# MCU.net
KiCad netlist of a schematic drawn in Altium Designer
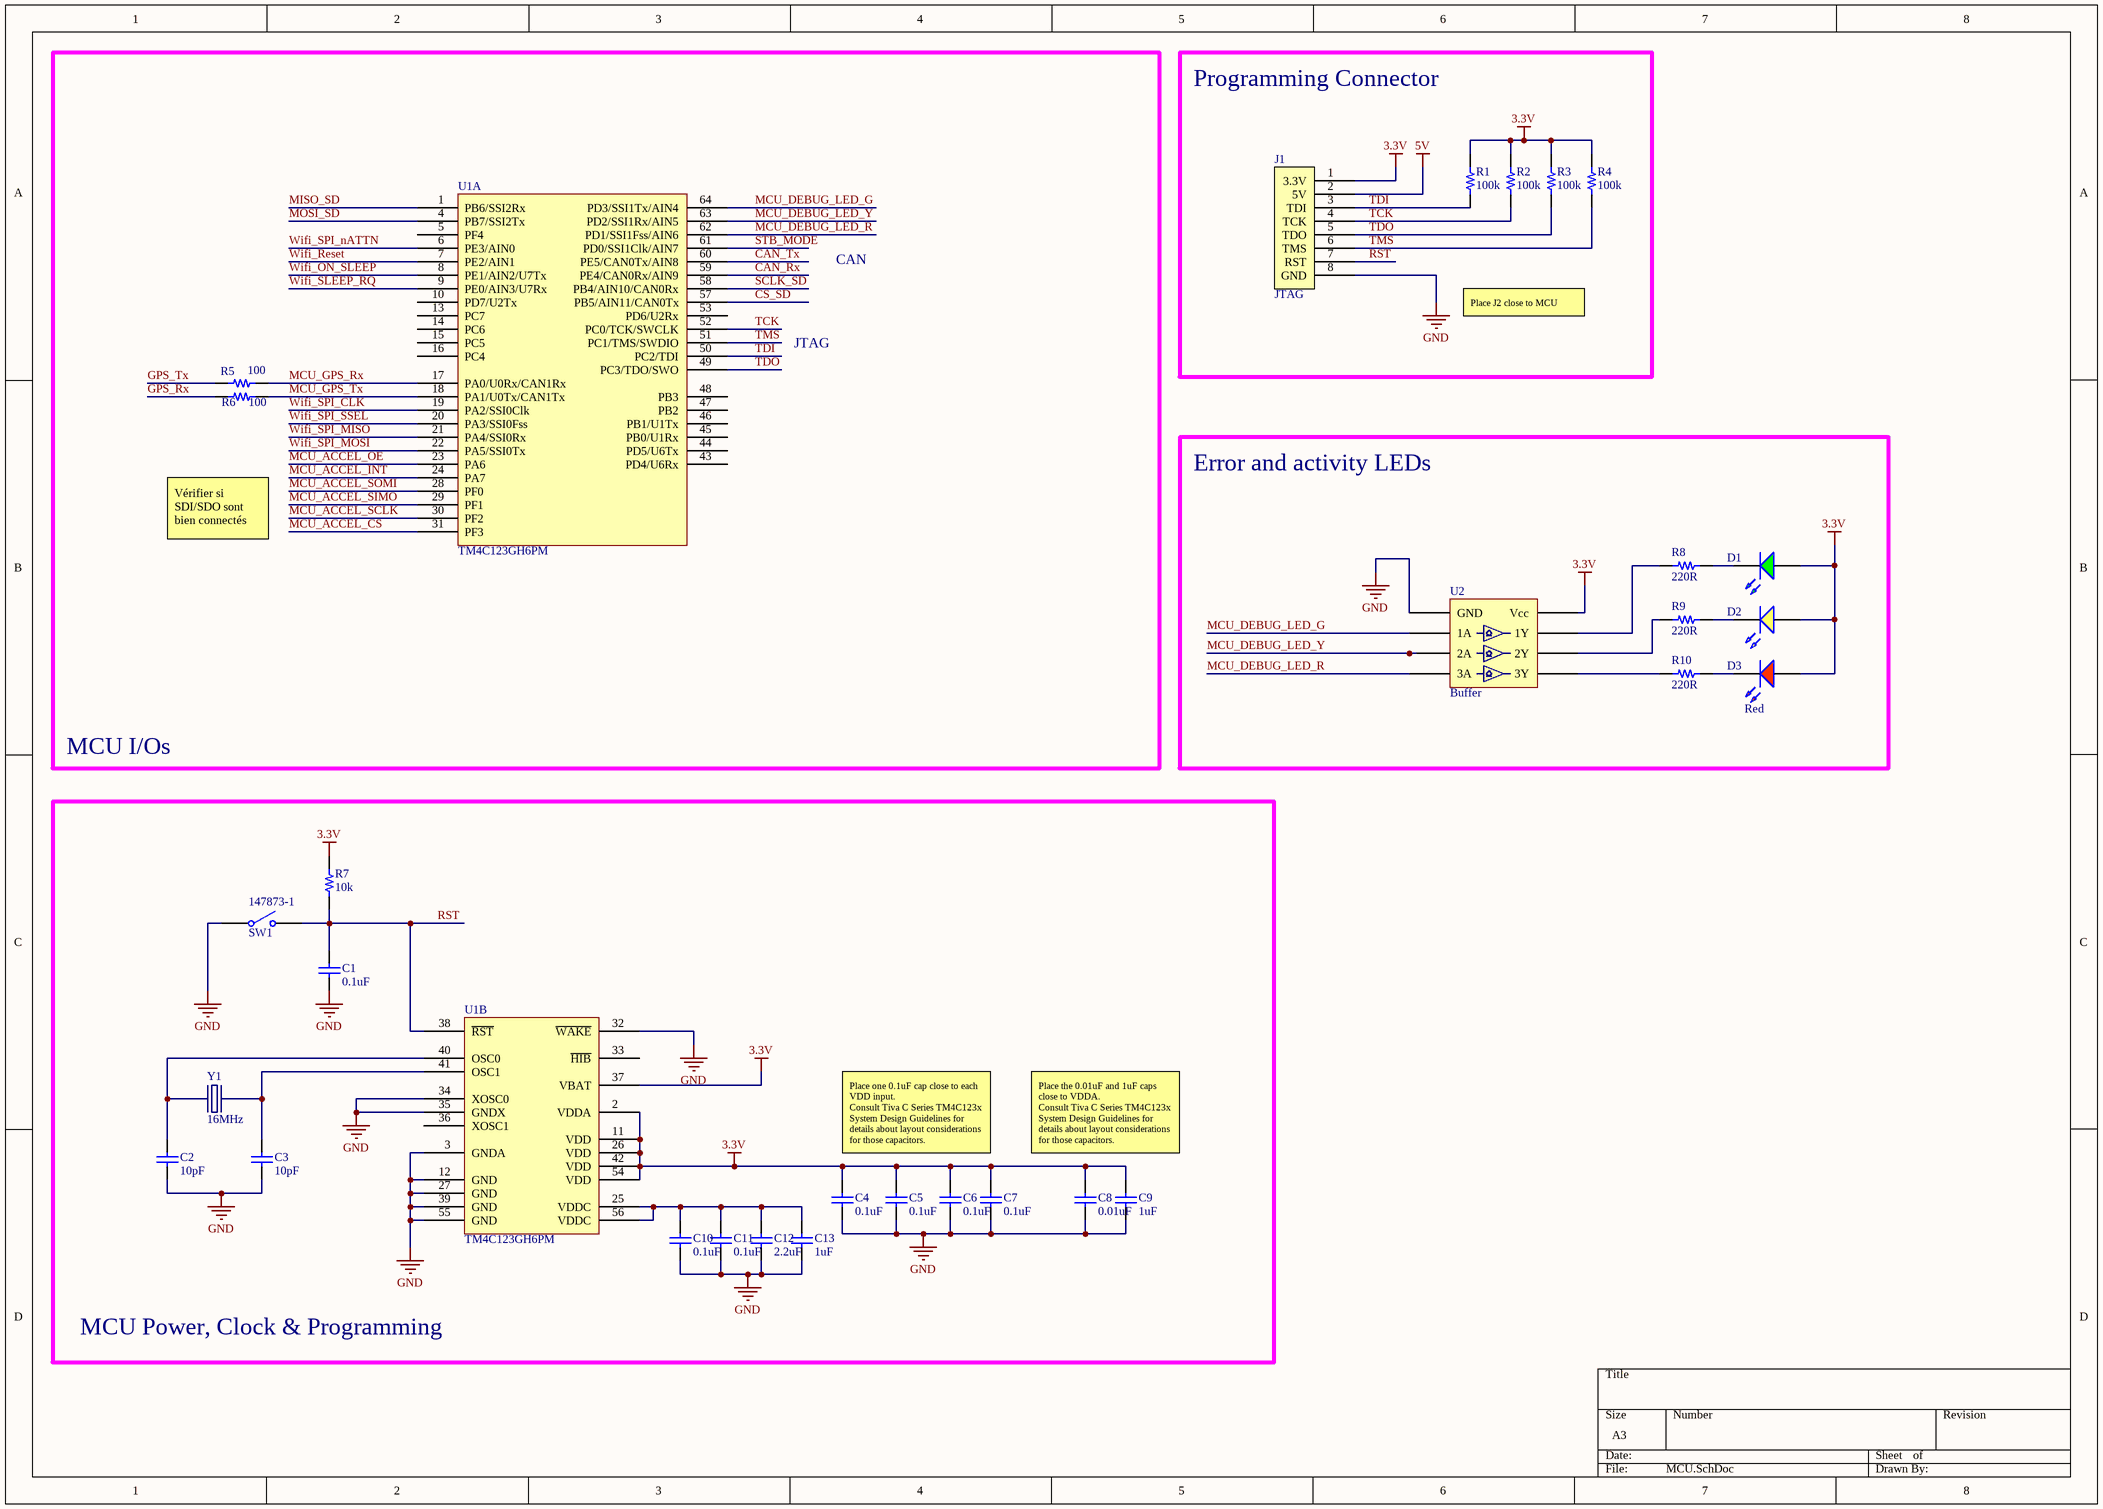
[diagram p0: MCU.SchDoc]

(export (version "E")
  (design (tool "Eeschema 10.0.6"))
  (components
    (comp (ref "C1")
      (value "0.1uF")
      (footprint "Capacitors:C0603")
      (description "0.1uF ceramic capacitor")
      (fields (field (name "MANUFACTURER") "TDK Corporation") (field (name "TOLERANCE") "10%"))
      (libsource (lib "Capacitors") (part "CAP CER 0603 0.1uF 50V C0G 10%"))
    )
    (comp (ref "C2")
      (value "10pF")
      (footprint "Capacitors:C0603")
      (description "10pF ceramic capacitor")
      (fields (field (name "MANUFACTURER") "TDK Corporation") (field (name "TOLERANCE") "5%"))
      (libsource (lib "Capacitors") (part "CAP CER 0603 10pF 50V C0G 5%"))
    )
    (comp (ref "C3")
      (value "10pF")
      (footprint "Capacitors:C0603")
      (description "10pF ceramic capacitor")
      (fields (field (name "MANUFACTURER") "TDK Corporation") (field (name "TOLERANCE") "5%"))
      (libsource (lib "Capacitors") (part "CAP CER 0603 10pF 50V C0G 5%"))
    )
    (comp (ref "C4")
      (value "0.1uF")
      (footprint "Capacitors:C0603")
      (description "0.1uF ceramic capacitor")
      (fields (field (name "MANUFACTURER") "TDK Corporation") (field (name "TOLERANCE") "10%"))
      (libsource (lib "Capacitors") (part "CAP CER 0603 0.1uF 50V C0G 10%"))
    )
    (comp (ref "C5")
      (value "0.1uF")
      (footprint "Capacitors:C0603")
      (description "0.1uF ceramic capacitor")
      (fields (field (name "MANUFACTURER") "TDK Corporation") (field (name "TOLERANCE") "10%"))
      (libsource (lib "Capacitors") (part "CAP CER 0603 0.1uF 50V C0G 10%"))
    )
    (comp (ref "C6")
      (value "0.1uF")
      (footprint "Capacitors:C0603")
      (description "0.1uF ceramic capacitor")
      (fields (field (name "MANUFACTURER") "TDK Corporation") (field (name "TOLERANCE") "10%"))
      (libsource (lib "Capacitors") (part "CAP CER 0603 0.1uF 50V C0G 10%"))
    )
    (comp (ref "C7")
      (value "0.1uF")
      (footprint "Capacitors:C0603")
      (description "0.1uF ceramic capacitor")
      (fields (field (name "MANUFACTURER") "TDK Corporation") (field (name "TOLERANCE") "10%"))
      (libsource (lib "Capacitors") (part "CAP CER 0603 0.1uF 50V C0G 10%"))
    )
    (comp (ref "C8")
      (value "0.01uF")
      (footprint "Capacitors:C0603")
      (description "0.01uF ceramic capacitor")
      (fields (field (name "MANUFACTURER") "TDK Corporation") (field (name "TOLERANCE") "10%"))
      (libsource (lib "Capacitors") (part "CAP CER 0603 0.01uF 50V X7R 10%"))
    )
    (comp (ref "C9")
      (value "1uF")
      (footprint "Capacitors:C0603")
      (description "1uF ceramic capacitor")
      (fields (field (name "MANUFACTURER") "TDK Corporation") (field (name "TOLERANCE") "20%"))
      (libsource (lib "Capacitors") (part "CAP CER 0603 1uF 25V X7R 20%"))
    )
    (comp (ref "C10")
      (value "0.1uF")
      (footprint "Capacitors:C0603")
      (description "0.1uF ceramic capacitor")
      (fields (field (name "MANUFACTURER") "TDK Corporation") (field (name "TOLERANCE") "10%"))
      (libsource (lib "Capacitors") (part "CAP CER 0603 0.1uF 50V C0G 10%"))
    )
    (comp (ref "C11")
      (value "0.1uF")
      (footprint "Capacitors:C0603")
      (description "0.1uF ceramic capacitor")
      (fields (field (name "MANUFACTURER") "TDK Corporation") (field (name "TOLERANCE") "10%"))
      (libsource (lib "Capacitors") (part "CAP CER 0603 0.1uF 50V C0G 10%"))
    )
    (comp (ref "C12")
      (value "2.2uF")
      (footprint "Capacitors:C0603")
      (description "2.2uF ceramic capacitor")
      (fields (field (name "MANUFACTURER") "TDK Corporation") (field (name "TOLERANCE") "10%"))
      (libsource (lib "Capacitors") (part "CAP CER 0603 2.2uF 6.3V X7R 10%"))
    )
    (comp (ref "C13")
      (value "1uF")
      (footprint "Capacitors:C0603")
      (description "1uF ceramic capacitor")
      (fields (field (name "MANUFACTURER") "TDK Corporation") (field (name "TOLERANCE") "20%"))
      (libsource (lib "Capacitors") (part "CAP CER 0603 1uF 25V X7R 20%"))
    )
    (comp (ref "D1")
      (value "Green LED")
      (footprint "LED1206")
      (description "Green LED 1206")
      (fields (field (name "MANUFACTURER") "Liteon") (field (name "PART_NUMBER") "LTST-C150KGKT"))
      (libsource (lib "Diodes") (part "LTST-C150KGKT"))
    )
    (comp (ref "D2")
      (value "Yellow")
      (footprint "LED1206")
      (description "Yellow LED 1206")
      (fields (field (name "MANUFACTURER") "Liteon") (field (name "PART_NUMBER") "LTST-C150KSKT"))
      (libsource (lib "Diodes") (part "LTST-C150KSKT"))
    )
    (comp (ref "D3")
      (value "Red")
      (footprint "LED1206")
      (description "Red LED 1206")
      (fields (field (name "MANUFACTURER") "Liteon") (field (name "PART_NUMBER") "LTST-C150KRKT"))
      (libsource (lib "Diodes") (part "LTST-C150KRKT"))
    )
    (comp (ref "J1")
      (value "JTAG")
      (footprint "Connectors:JTAG_Header")
      (description "JTAG header, MCU programming")
      (libsource (lib "Connectors") (part "JTAG_Header"))
    )
    (comp (ref "R1")
      (value "100k")
      (footprint "Resistors:R0603")
      (description "100 kOhm resistor")
      (fields (field (name "PART_NUMBER") "CRCW0603100KJNEA") (field (name "MANUFACTURER") "Vishay"))
      (libsource (lib "Resistors") (part "RES 0603 100k 5% 0.1W"))
    )
    (comp (ref "R2")
      (value "100k")
      (footprint "Resistors:R0603")
      (description "100 kOhm resistor")
      (fields (field (name "PART_NUMBER") "CRCW0603100KJNEA") (field (name "MANUFACTURER") "Vishay"))
      (libsource (lib "Resistors") (part "RES 0603 100k 5% 0.1W"))
    )
    (comp (ref "R3")
      (value "100k")
      (footprint "Resistors:R0603")
      (description "100 kOhm resistor")
      (fields (field (name "PART_NUMBER") "CRCW0603100KJNEA") (field (name "MANUFACTURER") "Vishay"))
      (libsource (lib "Resistors") (part "RES 0603 100k 5% 0.1W"))
    )
    (comp (ref "R4")
      (value "100k")
      (footprint "Resistors:R0603")
      (description "100 kOhm resistor")
      (fields (field (name "PART_NUMBER") "CRCW0603100KJNEA") (field (name "MANUFACTURER") "Vishay"))
      (libsource (lib "Resistors") (part "RES 0603 100k 5% 0.1W"))
    )
    (comp (ref "R5")
      (value "100")
      (footprint "Resistors:R0603")
      (description "100 Ohms resistor, 1/4W")
      (fields (field (name "PART_NUMBER") "ESR03EZPJ101") (field (name "MANUFACTURER") "Rohm Semiconductor"))
      (libsource (lib "Resistors") (part "RES 0603 100R 5% 1/4W"))
    )
    (comp (ref "R6")
      (value "100")
      (footprint "Resistors:R0603")
      (description "100 Ohms resistor, 1/4W")
      (fields (field (name "PART_NUMBER") "ESR03EZPJ101") (field (name "MANUFACTURER") "Rohm Semiconductor"))
      (libsource (lib "Resistors") (part "RES 0603 100R 5% 1/4W"))
    )
    (comp (ref "R7")
      (value "10k")
      (footprint "Resistors:R0603")
      (description "10 kOhms resistor")
      (fields (field (name "PART_NUMBER") "CRCW060310K0JNEA") (field (name "MANUFACTURER") "Vishay"))
      (libsource (lib "Resistors") (part "RES 0603 10k 5% 0.1W"))
    )
    (comp (ref "R8")
      (value "220R")
      (footprint "R0603")
      (description "220 Ohms 0.25W Resistor")
      (fields (field (name "PART_NUMBER") "ESR03EZPJ221") (field (name "MANUFACTURER") "Rohm Semiconductor"))
      (libsource (lib "Resistors") (part "RES 0603 220R 5% 0.25W"))
    )
    (comp (ref "R9")
      (value "220R")
      (footprint "R0603")
      (description "220 Ohms 0.25W Resistor")
      (fields (field (name "PART_NUMBER") "ESR03EZPJ221") (field (name "MANUFACTURER") "Rohm Semiconductor"))
      (libsource (lib "Resistors") (part "RES 0603 220R 5% 0.25W"))
    )
    (comp (ref "R10")
      (value "220R")
      (footprint "R0603")
      (description "220 Ohms 0.25W Resistor")
      (fields (field (name "PART_NUMBER") "ESR03EZPJ221") (field (name "MANUFACTURER") "Rohm Semiconductor"))
      (libsource (lib "Resistors") (part "RES 0603 220R 5% 0.25W"))
    )
    (comp (ref "SW1")
      (value "147873-1")
      (footprint "Other:147873")
      (description "Pushbutton switch SPST, 2 pins")
      (fields (field (name "MANUFACTURER") "TE Connectivity"))
      (libsource (lib "Other") (part "147873-1"))
    )
    (comp (ref "U1")
      (value "32-bit MCU")
      (footprint "LQFP-64")
      (description "High performance 32-bit ARM® Cortex®-M4F based MCU")
      (fields (field (name "MANUFACTURER") "Texas Instruments") (field (name "PART_NUMBER") "TM4C123GH6PM"))
      (libsource (lib "IC") (part "TM4C123GH6PM"))
    )
    (comp (ref "U2")
      (value "Buffer")
      (footprint "8-VFSOP - TI - DCM (S-PDSO-G8)")
      (description "Triple Buffer/Driver  With Open-drain Outputs")
      (fields
        (field (name "MANUFACTURER") "Texas Instrument")
        (field (name "PART_NUMBER") "SN74LVC3G07QDCURQ1")
      )
      (libsource (lib "IC") (part "SN74LVC3G07-Q1"))
    )
    (comp (ref "Y1")
      (value "16MHz")
      (footprint "NX5032GA")
      (description "Crystal Oscillator 16 MHz")
      (fields (field (name "MANUFACTURER") "NDK") (field (name "PART_NUMBER") "NX5032GA-16.000M-LN-CD-1"))
      (libsource (lib "Other") (part "NX5043GA-16.00MHz"))
    )
  )
  (nets
    (net (code "1") (name "/CAN_Rx") (class "Default")
      (node (ref "U1") (pin "59") (pinfunction "PE4/CAN0Rx/AIN9_59") (pintype "passive"))
    )
    (net (code "2") (name "/CAN_Tx") (class "Default")
      (node (ref "U1") (pin "60") (pinfunction "PE5/CAN0Tx/AIN8_60") (pintype "passive"))
    )
    (net (code "3") (name "/CS_SD") (class "Default")
      (node (ref "U1") (pin "57") (pinfunction "PB5/AIN11/CAN0Tx_57") (pintype "passive"))
    )
    (net (code "4") (name "/GPS_Rx") (class "Default")
      (node (ref "R6") (pin "2") (pinfunction "2_2") (pintype "passive"))
    )
    (net (code "5") (name "/GPS_Tx") (class "Default")
      (node (ref "R5") (pin "2") (pinfunction "2_2") (pintype "passive"))
    )
    (net (code "6") (name "/MCU_ACCEL_CS") (class "Default")
      (node (ref "U1") (pin "31") (pinfunction "PF3_31") (pintype "passive"))
    )
    (net (code "7") (name "/MCU_ACCEL_INT") (class "Default")
      (node (ref "U1") (pin "24") (pinfunction "PA7_24") (pintype "passive"))
    )
    (net (code "8") (name "/MCU_ACCEL_OE") (class "Default")
      (node (ref "U1") (pin "23") (pinfunction "PA6_23") (pintype "passive"))
    )
    (net (code "9") (name "/MCU_ACCEL_SCLK") (class "Default")
      (node (ref "U1") (pin "30") (pinfunction "PF2_30") (pintype "passive"))
    )
    (net (code "10") (name "/MCU_ACCEL_SIMO") (class "Default")
      (node (ref "U1") (pin "29") (pinfunction "PF1_29") (pintype "passive"))
    )
    (net (code "11") (name "/MCU_ACCEL_SOMI") (class "Default")
      (node (ref "U1") (pin "28") (pinfunction "PF0_28") (pintype "passive"))
    )
    (net (code "12") (name "/MCU_DEBUG_LED_G") (class "Default")
      (node (ref "U1") (pin "64") (pinfunction "PD3/SSI1Tx/AIN4_64") (pintype "passive"))
      (node (ref "U2") (pin "1") (pinfunction "1A_1") (pintype "passive"))
    )
    (net (code "13") (name "/MCU_DEBUG_LED_R") (class "Default")
      (node (ref "U1") (pin "62") (pinfunction "PD1/SSI1Fss/AIN6_62") (pintype "passive"))
      (node (ref "U2") (pin "6") (pinfunction "3A_6") (pintype "passive"))
    )
    (net (code "14") (name "/MCU_DEBUG_LED_Y") (class "Default")
      (node (ref "U1") (pin "63") (pinfunction "PD2/SSI1Rx/AIN5_63") (pintype "passive"))
      (node (ref "U2") (pin "3") (pinfunction "2A_3") (pintype "passive"))
    )
    (net (code "15") (name "/MCU_GPS_Rx") (class "Default")
      (node (ref "R5") (pin "1") (pinfunction "1_1") (pintype "passive"))
      (node (ref "U1") (pin "17") (pinfunction "PA0/U0Rx/CAN1Rx_17") (pintype "passive"))
    )
    (net (code "16") (name "/MCU_GPS_Tx") (class "Default")
      (node (ref "R6") (pin "1") (pinfunction "1_1") (pintype "passive"))
      (node (ref "U1") (pin "18") (pinfunction "PA1/U0Tx/CAN1Tx_18") (pintype "passive"))
    )
    (net (code "17") (name "/MISO_SD") (class "Default")
      (node (ref "U1") (pin "1") (pinfunction "PB6/SSI2Rx_1") (pintype "passive"))
    )
    (net (code "18") (name "/MOSI_SD") (class "Default")
      (node (ref "U1") (pin "4") (pinfunction "PB7/SSI2Tx_4") (pintype "passive"))
    )
    (net (code "19") (name "/RST") (class "Default")
      (node (ref "C1") (pin "2") (pinfunction "2_2") (pintype "passive"))
      (node (ref "J1") (pin "7") (pinfunction "RST_7") (pintype "passive"))
      (node (ref "R7") (pin "1") (pinfunction "1_1") (pintype "passive"))
      (node (ref "SW1") (pin "2") (pinfunction "NO_2") (pintype "passive"))
      (node (ref "U1") (pin "38") (pinfunction "~{RST}_38") (pintype "passive"))
    )
    (net (code "20") (name "/SCLK_SD") (class "Default")
      (node (ref "U1") (pin "58") (pinfunction "PB4/AIN10/CAN0Rx_58") (pintype "passive"))
    )
    (net (code "21") (name "/STB_MODE") (class "Default")
      (node (ref "U1") (pin "61") (pinfunction "PD0/SSI1Clk/AIN7_61") (pintype "passive"))
    )
    (net (code "22") (name "/TCK") (class "Default")
      (node (ref "J1") (pin "4") (pinfunction "TCK_4") (pintype "passive"))
      (node (ref "R2") (pin "1") (pinfunction "1_1") (pintype "passive"))
      (node (ref "U1") (pin "52") (pinfunction "PC0/TCK/SWCLK_52") (pintype "passive"))
    )
    (net (code "23") (name "/TDI") (class "Default")
      (node (ref "J1") (pin "3") (pinfunction "TDI_3") (pintype "passive"))
      (node (ref "R1") (pin "1") (pinfunction "1_1") (pintype "passive"))
      (node (ref "U1") (pin "50") (pinfunction "PC2/TDI_50") (pintype "passive"))
    )
    (net (code "24") (name "/TDO") (class "Default")
      (node (ref "J1") (pin "5") (pinfunction "TDO_5") (pintype "passive"))
      (node (ref "R3") (pin "1") (pinfunction "1_1") (pintype "passive"))
      (node (ref "U1") (pin "49") (pinfunction "PC3/TDO/SWO_49") (pintype "passive"))
    )
    (net (code "25") (name "/TMS") (class "Default")
      (node (ref "J1") (pin "6") (pinfunction "TMS_6") (pintype "passive"))
      (node (ref "R4") (pin "1") (pinfunction "1_1") (pintype "passive"))
      (node (ref "U1") (pin "51") (pinfunction "PC1/TMS/SWDIO_51") (pintype "passive"))
    )
    (net (code "26") (name "/Wifi_ON_SLEEP") (class "Default")
      (node (ref "U1") (pin "8") (pinfunction "PE1/AIN2/U7Tx_8") (pintype "passive"))
    )
    (net (code "27") (name "/Wifi_Reset") (class "Default")
      (node (ref "U1") (pin "7") (pinfunction "PE2/AIN1_7") (pintype "passive"))
    )
    (net (code "28") (name "/Wifi_SLEEP_RQ") (class "Default")
      (node (ref "U1") (pin "9") (pinfunction "PE0/AIN3/U7Rx_9") (pintype "passive"))
    )
    (net (code "29") (name "/Wifi_SPI_CLK") (class "Default")
      (node (ref "U1") (pin "19") (pinfunction "PA2/SSI0Clk_19") (pintype "passive"))
    )
    (net (code "30") (name "/Wifi_SPI_MISO") (class "Default")
      (node (ref "U1") (pin "21") (pinfunction "PA4/SSI0Rx_21") (pintype "passive"))
    )
    (net (code "31") (name "/Wifi_SPI_MOSI") (class "Default")
      (node (ref "U1") (pin "22") (pinfunction "PA5/SSI0Tx_22") (pintype "passive"))
    )
    (net (code "32") (name "/Wifi_SPI_SSEL") (class "Default")
      (node (ref "U1") (pin "20") (pinfunction "PA3/SSI0Fss_20") (pintype "passive"))
    )
    (net (code "33") (name "/Wifi_SPI_nATTN") (class "Default")
      (node (ref "U1") (pin "6") (pinfunction "PE3/AIN0_6") (pintype "passive"))
    )
    (net (code "34") (name "3.3V") (class "Default")
      (node (ref "C4") (pin "2") (pinfunction "2_2") (pintype "passive"))
      (node (ref "C5") (pin "2") (pinfunction "2_2") (pintype "passive"))
      (node (ref "C6") (pin "2") (pinfunction "2_2") (pintype "passive"))
      (node (ref "C7") (pin "2") (pinfunction "2_2") (pintype "passive"))
      (node (ref "C8") (pin "2") (pinfunction "2_2") (pintype "passive"))
      (node (ref "C9") (pin "2") (pinfunction "2_2") (pintype "passive"))
      (node (ref "D1") (pin "1") (pinfunction "A_1") (pintype "passive"))
      (node (ref "D2") (pin "1") (pinfunction "A_1") (pintype "passive"))
      (node (ref "D3") (pin "1") (pinfunction "A_1") (pintype "passive"))
      (node (ref "J1") (pin "1") (pinfunction "3.3V_1") (pintype "passive"))
      (node (ref "R1") (pin "2") (pinfunction "2_2") (pintype "passive"))
      (node (ref "R2") (pin "2") (pinfunction "2_2") (pintype "passive"))
      (node (ref "R3") (pin "2") (pinfunction "2_2") (pintype "passive"))
      (node (ref "R4") (pin "2") (pinfunction "2_2") (pintype "passive"))
      (node (ref "R7") (pin "2") (pinfunction "2_2") (pintype "passive"))
      (node (ref "U1") (pin "11") (pinfunction "VDD_11") (pintype "passive"))
      (node (ref "U1") (pin "2") (pinfunction "VDDA_2") (pintype "passive"))
      (node (ref "U1") (pin "26") (pinfunction "VDD_26") (pintype "passive"))
      (node (ref "U1") (pin "37") (pinfunction "VBAT_37") (pintype "passive"))
      (node (ref "U1") (pin "42") (pinfunction "VDD_42") (pintype "passive"))
      (node (ref "U1") (pin "54") (pinfunction "VDD_54") (pintype "passive"))
      (node (ref "U2") (pin "8") (pinfunction "Vcc_8") (pintype "passive"))
    )
    (net (code "35") (name "5V") (class "Default")
      (node (ref "J1") (pin "2") (pinfunction "5V_2") (pintype "passive"))
    )
    (net (code "36") (name "GND") (class "Default")
      (node (ref "C1") (pin "1") (pinfunction "1_1") (pintype "passive"))
      (node (ref "C10") (pin "1") (pinfunction "1_1") (pintype "passive"))
      (node (ref "C11") (pin "1") (pinfunction "1_1") (pintype "passive"))
      (node (ref "C12") (pin "1") (pinfunction "1_1") (pintype "passive"))
      (node (ref "C13") (pin "1") (pinfunction "1_1") (pintype "passive"))
      (node (ref "C2") (pin "1") (pinfunction "1_1") (pintype "passive"))
      (node (ref "C3") (pin "1") (pinfunction "1_1") (pintype "passive"))
      (node (ref "C4") (pin "1") (pinfunction "1_1") (pintype "passive"))
      (node (ref "C5") (pin "1") (pinfunction "1_1") (pintype "passive"))
      (node (ref "C6") (pin "1") (pinfunction "1_1") (pintype "passive"))
      (node (ref "C7") (pin "1") (pinfunction "1_1") (pintype "passive"))
      (node (ref "C8") (pin "1") (pinfunction "1_1") (pintype "passive"))
      (node (ref "C9") (pin "1") (pinfunction "1_1") (pintype "passive"))
      (node (ref "J1") (pin "8") (pinfunction "GND_8") (pintype "passive"))
      (node (ref "SW1") (pin "1") (pinfunction "COMMON_1") (pintype "passive"))
      (node (ref "U1") (pin "12") (pinfunction "GND_12") (pintype "passive"))
      (node (ref "U1") (pin "27") (pinfunction "GND_27") (pintype "passive"))
      (node (ref "U1") (pin "3") (pinfunction "GNDA_3") (pintype "passive"))
      (node (ref "U1") (pin "32") (pinfunction "~{WAKE}_32") (pintype "passive"))
      (node (ref "U1") (pin "34") (pinfunction "XOSC0_34") (pintype "passive"))
      (node (ref "U1") (pin "35") (pinfunction "GNDX_35") (pintype "passive"))
      (node (ref "U1") (pin "39") (pinfunction "GND_39") (pintype "passive"))
      (node (ref "U1") (pin "55") (pinfunction "GND_55") (pintype "passive"))
      (node (ref "U2") (pin "4") (pinfunction "GND_4") (pintype "passive"))
    )
    (net (code "37") (name "Net-(C10-Pad2)") (class "Default")
      (node (ref "C10") (pin "2") (pinfunction "2_2") (pintype "passive"))
      (node (ref "C11") (pin "2") (pinfunction "2_2") (pintype "passive"))
      (node (ref "C12") (pin "2") (pinfunction "2_2") (pintype "passive"))
      (node (ref "C13") (pin "2") (pinfunction "2_2") (pintype "passive"))
      (node (ref "U1") (pin "25") (pinfunction "VDDC_25") (pintype "passive"))
      (node (ref "U1") (pin "56") (pinfunction "VDDC_56") (pintype "passive"))
    )
    (net (code "38") (name "Net-(D1-K)") (class "Default")
      (node (ref "D1") (pin "2") (pinfunction "K_2") (pintype "passive"))
      (node (ref "R8") (pin "2") (pinfunction "2_2") (pintype "passive"))
    )
    (net (code "39") (name "Net-(D2-K)") (class "Default")
      (node (ref "D2") (pin "2") (pinfunction "K_2") (pintype "passive"))
      (node (ref "R9") (pin "2") (pinfunction "2_2") (pintype "passive"))
    )
    (net (code "40") (name "Net-(D3-K)") (class "Default")
      (node (ref "D3") (pin "2") (pinfunction "K_2") (pintype "passive"))
      (node (ref "R10") (pin "2") (pinfunction "2_2") (pintype "passive"))
    )
    (net (code "41") (name "Net-(U1B-OSC0)") (class "Default")
      (node (ref "C2") (pin "2") (pinfunction "2_2") (pintype "passive"))
      (node (ref "U1") (pin "40") (pinfunction "OSC0_40") (pintype "passive"))
      (node (ref "Y1") (pin "1") (pinfunction "1_1") (pintype "passive"))
    )
    (net (code "42") (name "Net-(U1B-OSC1)") (class "Default")
      (node (ref "C3") (pin "2") (pinfunction "2_2") (pintype "passive"))
      (node (ref "U1") (pin "41") (pinfunction "OSC1_41") (pintype "passive"))
      (node (ref "Y1") (pin "2") (pinfunction "2_2") (pintype "passive"))
    )
    (net (code "43") (name "Net-(U2-1Y)") (class "Default")
      (node (ref "R8") (pin "1") (pinfunction "1_1") (pintype "passive"))
      (node (ref "U2") (pin "7") (pinfunction "1Y_7") (pintype "passive"))
    )
    (net (code "44") (name "Net-(U2-2Y)") (class "Default")
      (node (ref "R9") (pin "1") (pinfunction "1_1") (pintype "passive"))
      (node (ref "U2") (pin "5") (pinfunction "2Y_5") (pintype "passive"))
    )
    (net (code "45") (name "Net-(U2-3Y)") (class "Default")
      (node (ref "R10") (pin "1") (pinfunction "1_1") (pintype "passive"))
      (node (ref "U2") (pin "2") (pinfunction "3Y_2") (pintype "passive"))
    )
    (net (code "46") (name "unconnected-(U1A-PB0{slash}U1Rx-Pad45)") (class "Default")
      (node (ref "U1") (pin "45") (pinfunction "PB0/U1Rx_45") (pintype "passive"))
    )
    (net (code "47") (name "unconnected-(U1A-PB1{slash}U1Tx-Pad46)") (class "Default")
      (node (ref "U1") (pin "46") (pinfunction "PB1/U1Tx_46") (pintype "passive"))
    )
    (net (code "48") (name "unconnected-(U1A-PB2-Pad47)") (class "Default")
      (node (ref "U1") (pin "47") (pinfunction "PB2_47") (pintype "passive"))
    )
    (net (code "49") (name "unconnected-(U1A-PB3-Pad48)") (class "Default")
      (node (ref "U1") (pin "48") (pinfunction "PB3_48") (pintype "passive"))
    )
    (net (code "50") (name "unconnected-(U1A-PC4-Pad16)") (class "Default")
      (node (ref "U1") (pin "16") (pinfunction "PC4_16") (pintype "passive"))
    )
    (net (code "51") (name "unconnected-(U1A-PC5-Pad15)") (class "Default")
      (node (ref "U1") (pin "15") (pinfunction "PC5_15") (pintype "passive"))
    )
    (net (code "52") (name "unconnected-(U1A-PC6-Pad14)") (class "Default")
      (node (ref "U1") (pin "14") (pinfunction "PC6_14") (pintype "passive"))
    )
    (net (code "53") (name "unconnected-(U1A-PC7-Pad13)") (class "Default")
      (node (ref "U1") (pin "13") (pinfunction "PC7_13") (pintype "passive"))
    )
    (net (code "54") (name "unconnected-(U1A-PD4{slash}U6Rx-Pad43)") (class "Default")
      (node (ref "U1") (pin "43") (pinfunction "PD4/U6Rx_43") (pintype "passive"))
    )
    (net (code "55") (name "unconnected-(U1A-PD5{slash}U6Tx-Pad44)") (class "Default")
      (node (ref "U1") (pin "44") (pinfunction "PD5/U6Tx_44") (pintype "passive"))
    )
    (net (code "56") (name "unconnected-(U1A-PD6{slash}U2Rx-Pad53)") (class "Default")
      (node (ref "U1") (pin "53") (pinfunction "PD6/U2Rx_53") (pintype "passive"))
    )
    (net (code "57") (name "unconnected-(U1A-PD7{slash}U2Tx-Pad10)") (class "Default")
      (node (ref "U1") (pin "10") (pinfunction "PD7/U2Tx_10") (pintype "passive"))
    )
    (net (code "58") (name "unconnected-(U1A-PF4-Pad5)") (class "Default")
      (node (ref "U1") (pin "5") (pinfunction "PF4_5") (pintype "passive"))
    )
    (net (code "59") (name "unconnected-(U1B-XOSC1-Pad36)") (class "Default")
      (node (ref "U1") (pin "36") (pinfunction "XOSC1_36") (pintype "passive"))
    )
    (net (code "60") (name "unconnected-(U1B-~{HIB}-Pad33)") (class "Default")
      (node (ref "U1") (pin "33") (pinfunction "~{HIB}_33") (pintype "passive"))
    )
  )
)
